# OV5640af.net
KiCad netlist of a schematic drawn in EAGLE
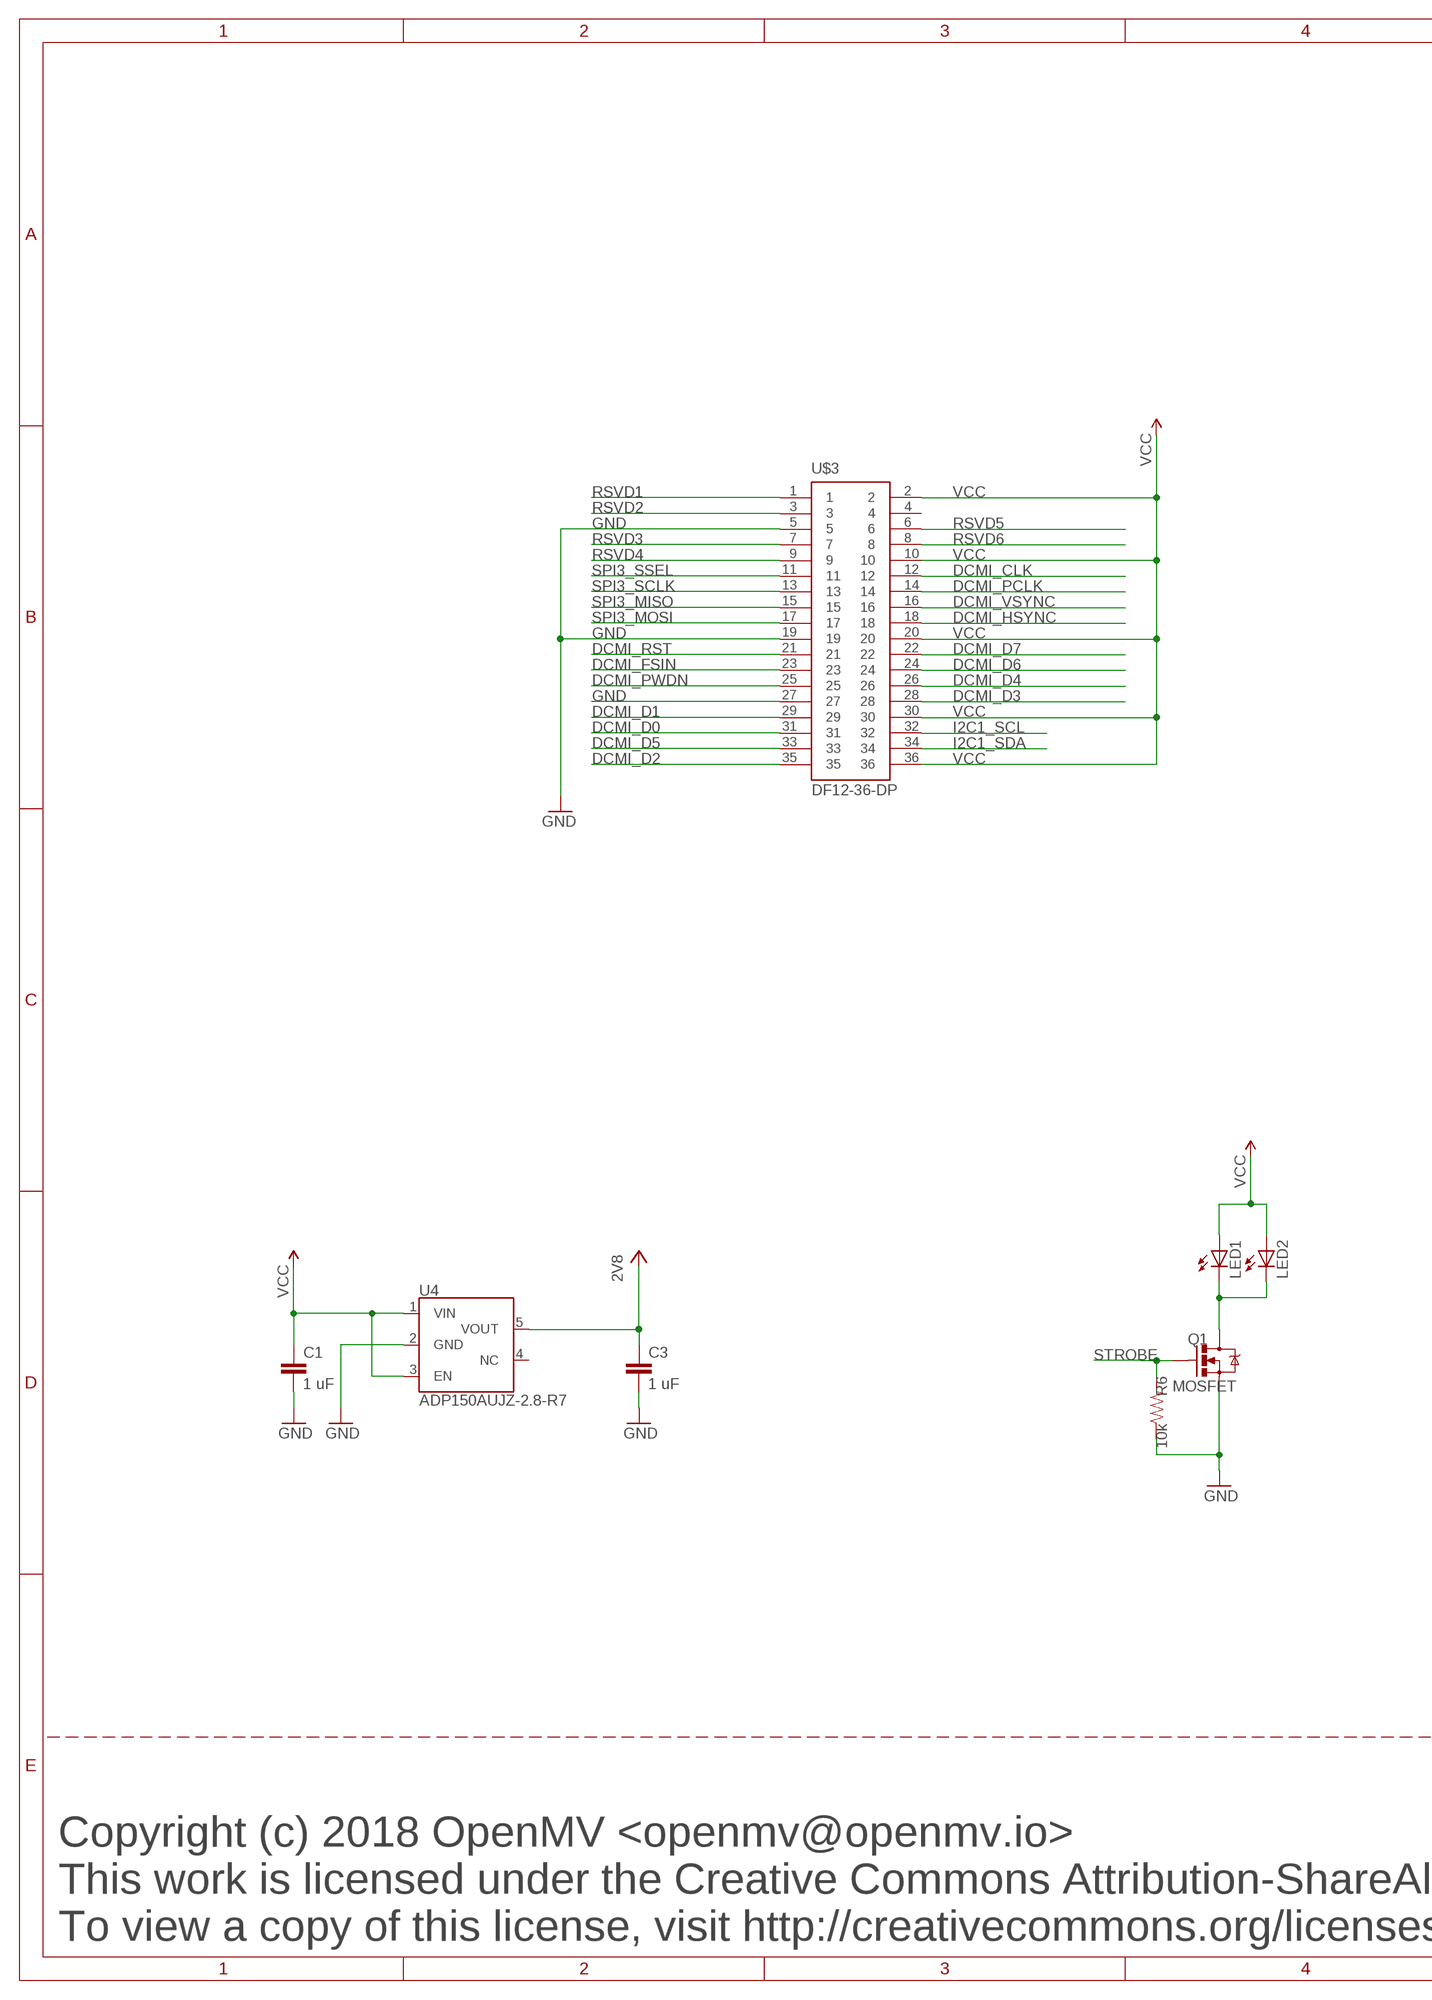
[diagram p0: schematic, sheet 1, part 1 of 2]
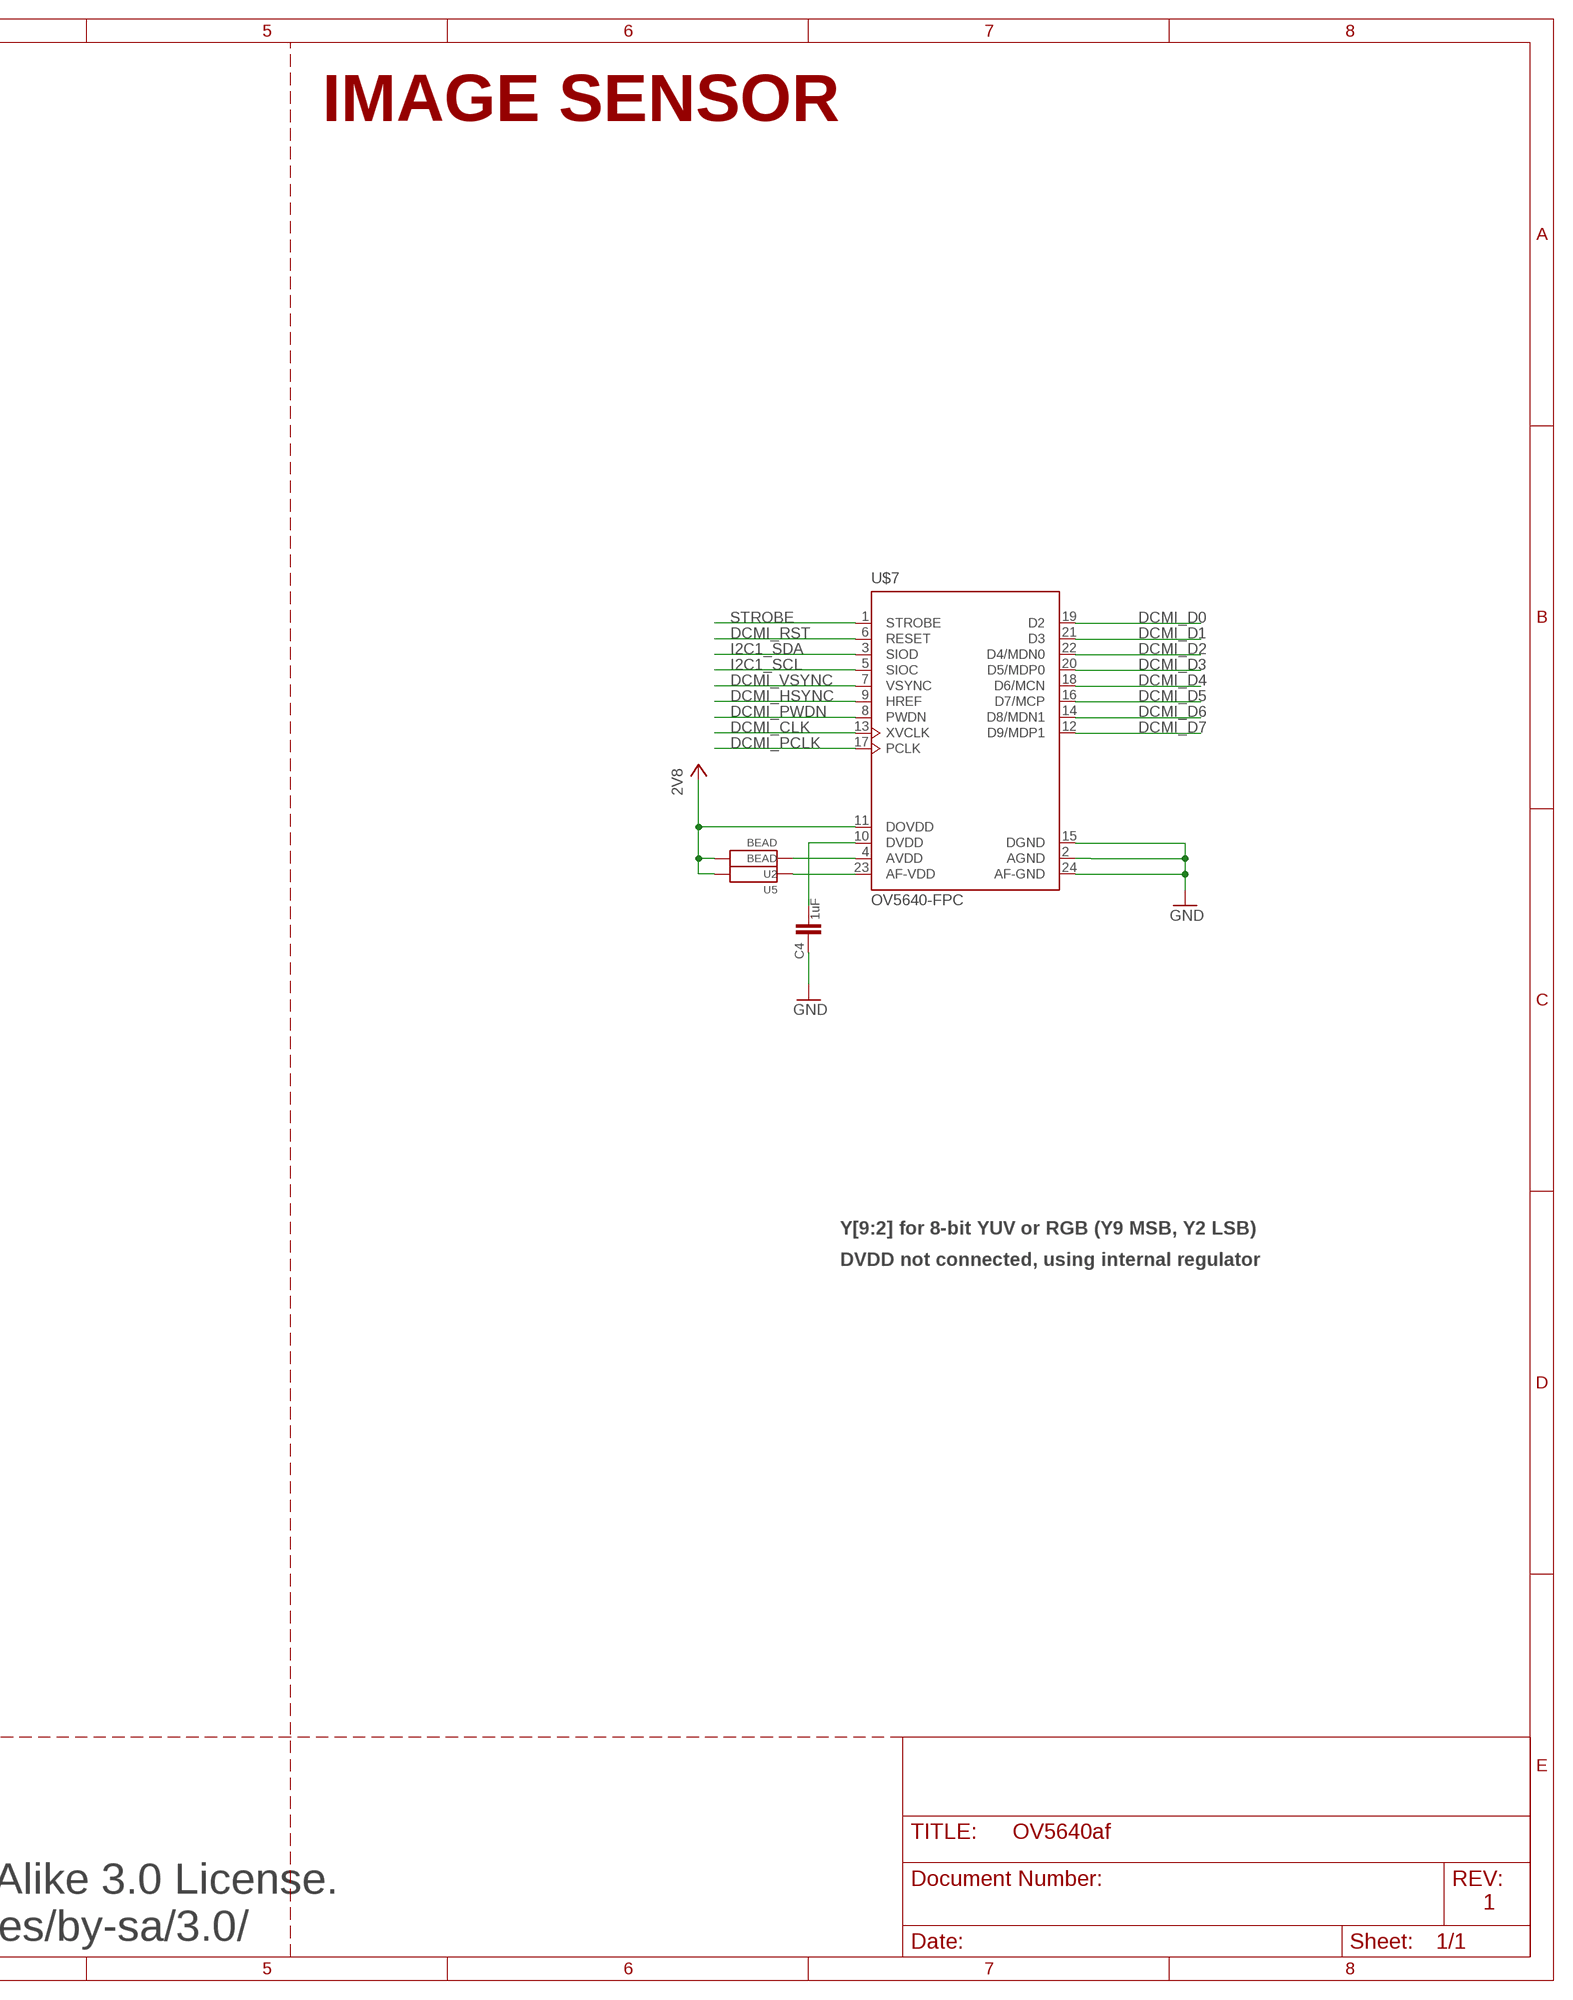
[diagram p1: schematic, sheet 1, part 2 of 2]

(export (version "E")
  (design (tool "Eeschema 10.0.6"))
  (components
    (comp (ref "C1")
      (value "1 uF")
      (footprint "eagle-import:0402-CAP")
      (libsource (lib "eagle-import") (part "CAP0402-CAP"))
    )
    (comp (ref "C3")
      (value "1 uF")
      (footprint "eagle-import:0402-CAP")
      (libsource (lib "eagle-import") (part "CAP0402-CAP"))
    )
    (comp (ref "C4")
      (value "1uF")
      (footprint "eagle-import:0402-CAP")
      (libsource (lib "eagle-import") (part "sfe_CAP0402-CAP"))
    )
    (comp (ref "LED1")
      (value "LEDCHIPLED_1206")
      (footprint "eagle-import:CHIPLED_1206")
      (libsource (lib "eagle-import") (part "LEDCHIPLED_1206"))
    )
    (comp (ref "LED2")
      (value "LEDCHIPLED_1206")
      (footprint "eagle-import:CHIPLED_1206")
      (libsource (lib "eagle-import") (part "LEDCHIPLED_1206"))
    )
    (comp (ref "Q1")
      (value "MOSFET")
      (footprint "eagle-import:SOT23-3")
      (libsource (lib "eagle-import") (part "MOSFET-NCHANNELSMD"))
    )
    (comp (ref "R6")
      (value "10k")
      (footprint "eagle-import:0603-RES")
      (libsource (lib "eagle-import") (part "RESISTOR0603-RES"))
    )
    (comp (ref "U$3")
      (value "DF12-36-DP")
      (footprint "eagle-import:DF12-36-DP")
      (libsource (lib "eagle-import") (part "DF12-36-DP"))
    )
    (comp (ref "U$7")
      (value "OV5640-FPC")
      (footprint "eagle-import:FPC24")
      (libsource (lib "eagle-import") (part "OV5640-FPC"))
    )
    (comp (ref "U2")
      (value "BEAD")
      (footprint "eagle-import:0402-CAP")
      (libsource (lib "eagle-import") (part "BEAD"))
    )
    (comp (ref "U4")
      (value "ADP150AUJZ-2.8-R7")
      (footprint "eagle-import:SOT23-5")
      (libsource (lib "eagle-import") (part "ADP150TSOT-5"))
    )
    (comp (ref "U5")
      (value "BEAD")
      (footprint "eagle-import:0402-CAP")
      (libsource (lib "eagle-import") (part "BEAD"))
    )
  )
  (nets
    (net (code "1") (name "/DCMI_CLK") (class "Default")
      (node (ref "U$3") (pin "12") (pinfunction "12_12") (pintype "bidirectional"))
      (node (ref "U$7") (pin "13") (pinfunction "XVCLK_13") (pintype "input"))
    )
    (net (code "2") (name "/DCMI_D0") (class "Default")
      (node (ref "U$3") (pin "31") (pinfunction "31_31") (pintype "bidirectional"))
      (node (ref "U$7") (pin "19") (pinfunction "D2_19") (pintype "bidirectional"))
    )
    (net (code "3") (name "/DCMI_D1") (class "Default")
      (node (ref "U$3") (pin "29") (pinfunction "29_29") (pintype "bidirectional"))
      (node (ref "U$7") (pin "21") (pinfunction "D3_21") (pintype "bidirectional"))
    )
    (net (code "4") (name "/DCMI_D2") (class "Default")
      (node (ref "U$3") (pin "35") (pinfunction "35_35") (pintype "bidirectional"))
      (node (ref "U$7") (pin "22") (pinfunction "D4/MDN0_22") (pintype "bidirectional"))
    )
    (net (code "5") (name "/DCMI_D3") (class "Default")
      (node (ref "U$3") (pin "28") (pinfunction "28_28") (pintype "bidirectional"))
      (node (ref "U$7") (pin "20") (pinfunction "D5/MDP0_20") (pintype "bidirectional"))
    )
    (net (code "6") (name "/DCMI_D4") (class "Default")
      (node (ref "U$3") (pin "26") (pinfunction "26_26") (pintype "bidirectional"))
      (node (ref "U$7") (pin "18") (pinfunction "D6/MCN_18") (pintype "bidirectional"))
    )
    (net (code "7") (name "/DCMI_D5") (class "Default")
      (node (ref "U$3") (pin "33") (pinfunction "33_33") (pintype "bidirectional"))
      (node (ref "U$7") (pin "16") (pinfunction "D7/MCP_16") (pintype "bidirectional"))
    )
    (net (code "8") (name "/DCMI_D6") (class "Default")
      (node (ref "U$3") (pin "24") (pinfunction "24_24") (pintype "bidirectional"))
      (node (ref "U$7") (pin "14") (pinfunction "D8/MDN1_14") (pintype "bidirectional"))
    )
    (net (code "9") (name "/DCMI_D7") (class "Default")
      (node (ref "U$3") (pin "22") (pinfunction "22_22") (pintype "bidirectional"))
      (node (ref "U$7") (pin "12") (pinfunction "D9/MDP1_12") (pintype "bidirectional"))
    )
    (net (code "10") (name "/DCMI_FSIN") (class "Default")
      (node (ref "U$3") (pin "23") (pinfunction "23_23") (pintype "bidirectional"))
    )
    (net (code "11") (name "/DCMI_HSYNC") (class "Default")
      (node (ref "U$3") (pin "18") (pinfunction "18_18") (pintype "bidirectional"))
      (node (ref "U$7") (pin "9") (pinfunction "HREF_9") (pintype "bidirectional"))
    )
    (net (code "12") (name "/DCMI_PCLK") (class "Default")
      (node (ref "U$3") (pin "14") (pinfunction "14_14") (pintype "bidirectional"))
      (node (ref "U$7") (pin "17") (pinfunction "PCLK_17") (pintype "bidirectional"))
    )
    (net (code "13") (name "/DCMI_PWDN") (class "Default")
      (node (ref "U$3") (pin "25") (pinfunction "25_25") (pintype "bidirectional"))
      (node (ref "U$7") (pin "8") (pinfunction "PWDN_8") (pintype "input"))
    )
    (net (code "14") (name "/DCMI_RST") (class "Default")
      (node (ref "U$3") (pin "21") (pinfunction "21_21") (pintype "bidirectional"))
      (node (ref "U$7") (pin "6") (pinfunction "RESET_6") (pintype "input"))
    )
    (net (code "15") (name "/DCMI_VSYNC") (class "Default")
      (node (ref "U$3") (pin "16") (pinfunction "16_16") (pintype "bidirectional"))
      (node (ref "U$7") (pin "7") (pinfunction "VSYNC_7") (pintype "bidirectional"))
    )
    (net (code "16") (name "/I2C1_SCL") (class "Default")
      (node (ref "U$3") (pin "32") (pinfunction "32_32") (pintype "bidirectional"))
      (node (ref "U$7") (pin "5") (pinfunction "SIOC_5") (pintype "input"))
    )
    (net (code "17") (name "/I2C1_SDA") (class "Default")
      (node (ref "U$3") (pin "34") (pinfunction "34_34") (pintype "bidirectional"))
      (node (ref "U$7") (pin "3") (pinfunction "SIOD_3") (pintype "bidirectional"))
    )
    (net (code "18") (name "/RSVD1") (class "Default")
      (node (ref "U$3") (pin "1") (pinfunction "1_1") (pintype "bidirectional"))
    )
    (net (code "19") (name "/RSVD2") (class "Default")
      (node (ref "U$3") (pin "3") (pinfunction "3_3") (pintype "bidirectional"))
    )
    (net (code "20") (name "/RSVD3") (class "Default")
      (node (ref "U$3") (pin "7") (pinfunction "7_7") (pintype "bidirectional"))
    )
    (net (code "21") (name "/RSVD4") (class "Default")
      (node (ref "U$3") (pin "9") (pinfunction "9_9") (pintype "bidirectional"))
    )
    (net (code "22") (name "/RSVD5") (class "Default")
      (node (ref "U$3") (pin "6") (pinfunction "6_6") (pintype "bidirectional"))
    )
    (net (code "23") (name "/RSVD6") (class "Default")
      (node (ref "U$3") (pin "8") (pinfunction "8_8") (pintype "bidirectional"))
    )
    (net (code "24") (name "/SPI3_MISO") (class "Default")
      (node (ref "U$3") (pin "15") (pinfunction "15_15") (pintype "bidirectional"))
    )
    (net (code "25") (name "/SPI3_MOSI") (class "Default")
      (node (ref "U$3") (pin "17") (pinfunction "17_17") (pintype "bidirectional"))
    )
    (net (code "26") (name "/SPI3_SCLK") (class "Default")
      (node (ref "U$3") (pin "13") (pinfunction "13_13") (pintype "bidirectional"))
    )
    (net (code "27") (name "/SPI3_SSEL") (class "Default")
      (node (ref "U$3") (pin "11") (pinfunction "11_11") (pintype "bidirectional"))
    )
    (net (code "28") (name "/STROBE") (class "Default")
      (node (ref "Q1") (pin "1") (pinfunction "G_1") (pintype "passive"))
      (node (ref "R6") (pin "2") (pinfunction "2_2") (pintype "passive"))
      (node (ref "U$7") (pin "1") (pinfunction "STROBE_1") (pintype "bidirectional"))
    )
    (net (code "29") (name "2V8") (class "Default")
      (node (ref "C3") (pin "1") (pinfunction "1_1") (pintype "passive"))
      (node (ref "U$7") (pin "11") (pinfunction "DOVDD_11") (pintype "power_in"))
      (node (ref "U2") (pin "2") (pinfunction "2_2") (pintype "passive"))
      (node (ref "U4") (pin "5") (pinfunction "VOUT_5") (pintype "power_in"))
      (node (ref "U5") (pin "2") (pinfunction "2_2") (pintype "passive"))
    )
    (net (code "30") (name "GND") (class "Default")
      (node (ref "C1") (pin "2") (pinfunction "2_2") (pintype "passive"))
      (node (ref "C3") (pin "2") (pinfunction "2_2") (pintype "passive"))
      (node (ref "C4") (pin "2") (pinfunction "2_2") (pintype "passive"))
      (node (ref "Q1") (pin "2") (pinfunction "S_2") (pintype "passive"))
      (node (ref "R6") (pin "1") (pinfunction "1_1") (pintype "passive"))
      (node (ref "U$3") (pin "19") (pinfunction "19_19") (pintype "bidirectional"))
      (node (ref "U$3") (pin "27") (pinfunction "27_27") (pintype "bidirectional"))
      (node (ref "U$3") (pin "5") (pinfunction "5_5") (pintype "bidirectional"))
      (node (ref "U$7") (pin "15") (pinfunction "DGND_15") (pintype "power_in"))
      (node (ref "U$7") (pin "2") (pinfunction "AGND_2") (pintype "power_in"))
      (node (ref "U$7") (pin "24") (pinfunction "AF-GND_24") (pintype "bidirectional"))
      (node (ref "U4") (pin "2") (pinfunction "GND_2") (pintype "power_in"))
    )
    (net (code "31") (name "Net-(Q1-D)") (class "Default")
      (node (ref "LED1") (pin "C") (pinfunction "C_C") (pintype "passive"))
      (node (ref "LED2") (pin "C") (pinfunction "C_C") (pintype "passive"))
      (node (ref "Q1") (pin "3") (pinfunction "D_3") (pintype "passive"))
    )
    (net (code "32") (name "Net-(U$7-AF-VDD)") (class "Default")
      (node (ref "U$7") (pin "23") (pinfunction "AF-VDD_23") (pintype "bidirectional"))
      (node (ref "U5") (pin "1") (pinfunction "1_1") (pintype "passive"))
    )
    (net (code "33") (name "Net-(U$7-AVDD)") (class "Default")
      (node (ref "U$7") (pin "4") (pinfunction "AVDD_4") (pintype "power_in"))
      (node (ref "U2") (pin "1") (pinfunction "1_1") (pintype "passive"))
    )
    (net (code "34") (name "Net-(U$7-DVDD)") (class "Default")
      (node (ref "C4") (pin "1") (pinfunction "1_1") (pintype "passive"))
      (node (ref "U$7") (pin "10") (pinfunction "DVDD_10") (pintype "power_in"))
    )
    (net (code "35") (name "VCC") (class "Default")
      (node (ref "C1") (pin "1") (pinfunction "1_1") (pintype "passive"))
      (node (ref "LED1") (pin "A") (pinfunction "A_A") (pintype "passive"))
      (node (ref "LED2") (pin "A") (pinfunction "A_A") (pintype "passive"))
      (node (ref "U$3") (pin "10") (pinfunction "10_10") (pintype "bidirectional"))
      (node (ref "U$3") (pin "2") (pinfunction "2_2") (pintype "bidirectional"))
      (node (ref "U$3") (pin "20") (pinfunction "20_20") (pintype "bidirectional"))
      (node (ref "U$3") (pin "30") (pinfunction "30_30") (pintype "bidirectional"))
      (node (ref "U$3") (pin "36") (pinfunction "36_36") (pintype "bidirectional"))
      (node (ref "U4") (pin "1") (pinfunction "VIN_1") (pintype "power_in"))
      (node (ref "U4") (pin "3") (pinfunction "EN_3") (pintype "bidirectional"))
    )
    (net (code "36") (name "unconnected-(U$3-Pad4)") (class "Default")
      (node (ref "U$3") (pin "4") (pinfunction "4_4") (pintype "bidirectional"))
    )
    (net (code "37") (name "unconnected-(U4-NC-Pad4)") (class "Default")
      (node (ref "U4") (pin "4") (pinfunction "NC_4") (pintype "bidirectional"))
    )
  )
)
